# uCBoard.net
KiCad netlist of a schematic drawn in EAGLE
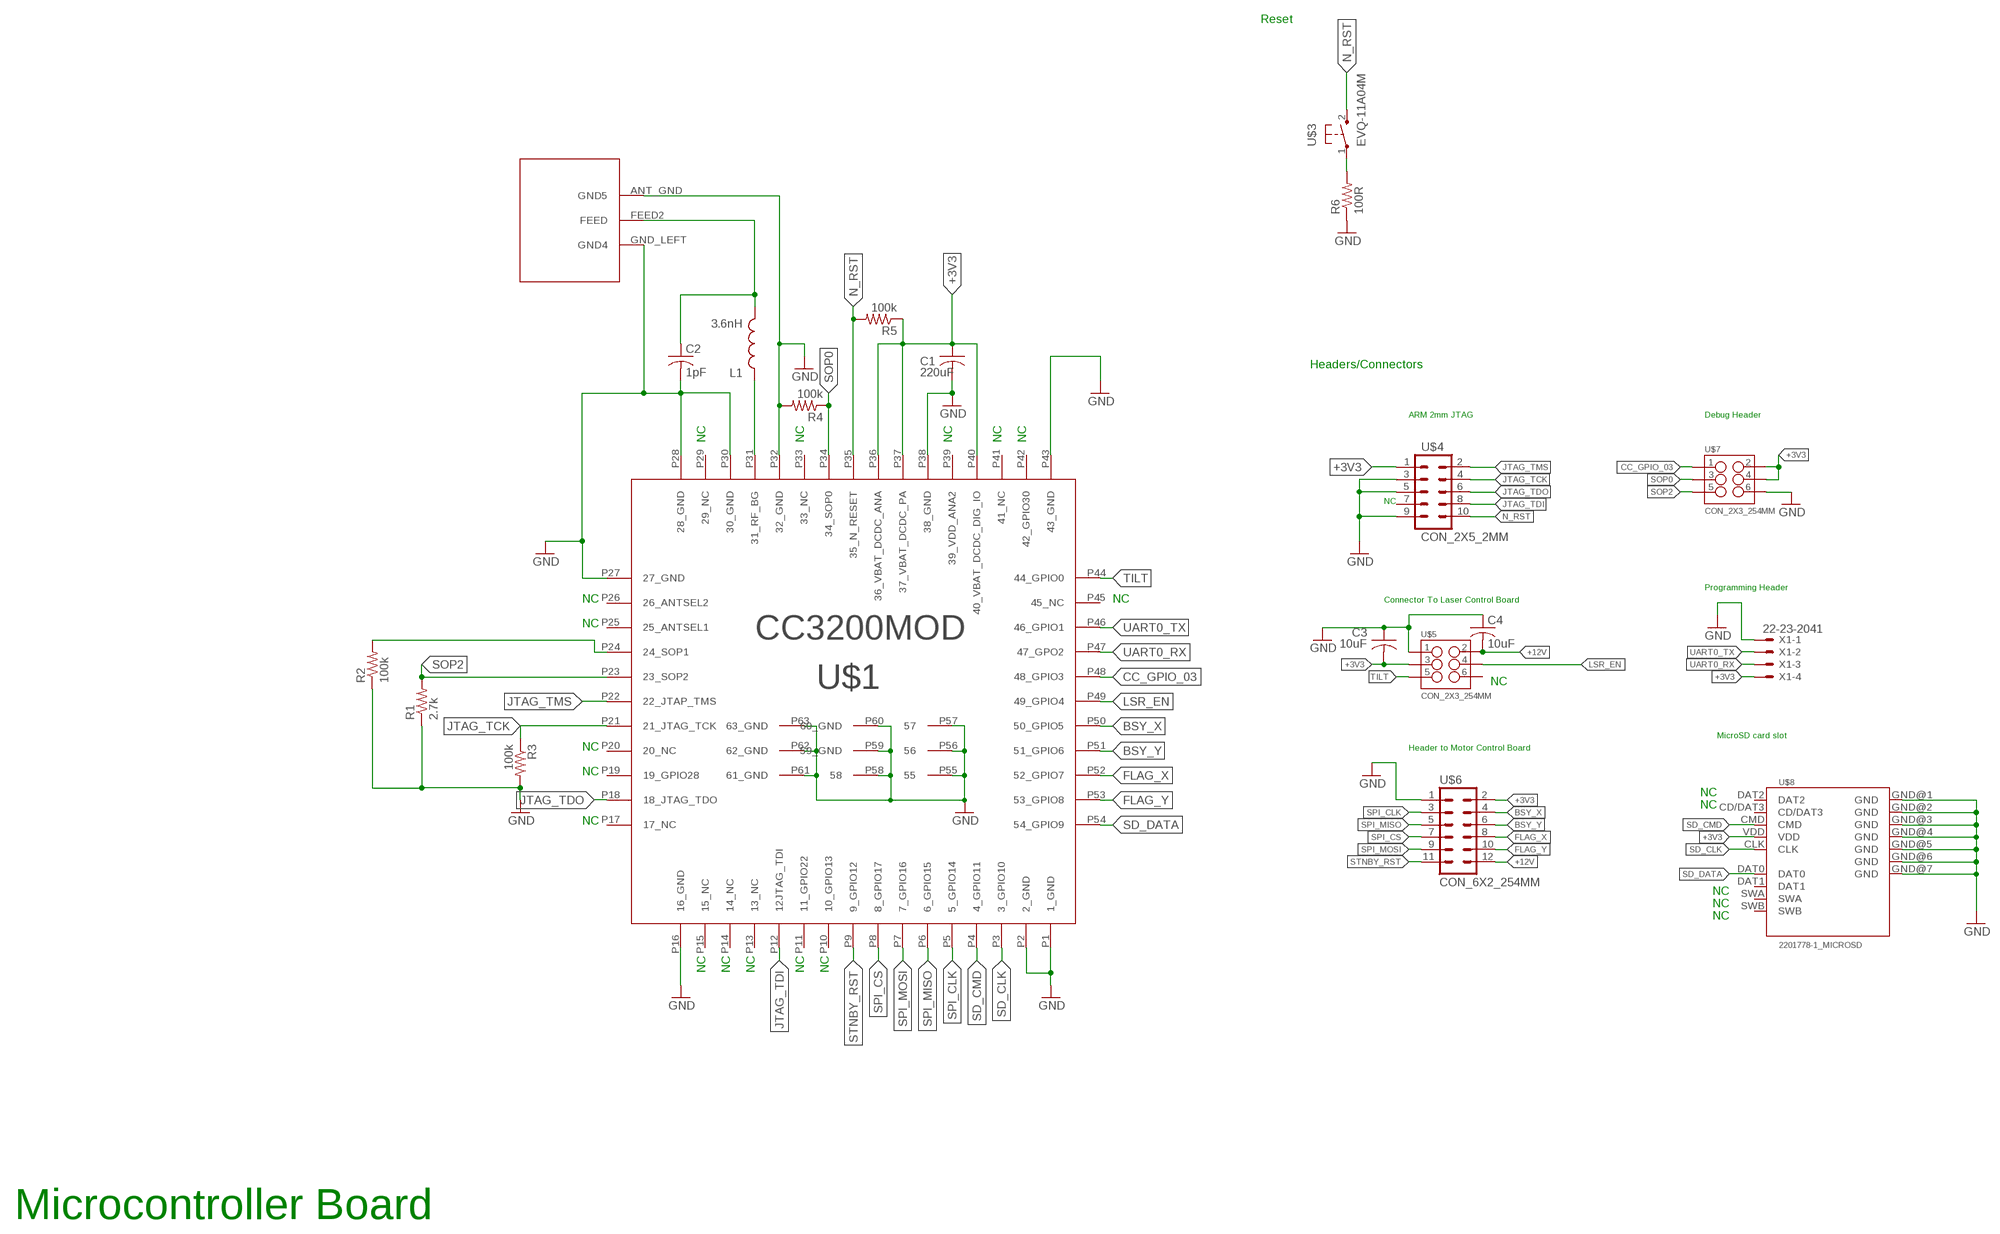
[diagram p0: schematic, sheet 1]

(export (version "E")
  (design (tool "Eeschema 10.0.6"))
  (components
    (comp (ref "C1")
      (value "220uF")
      (footprint "eagle-import:C1210")
      (libsource (lib "eagle-import") (part "C-USC1210"))
    )
    (comp (ref "C2")
      (value "1pF")
      (footprint "eagle-import:C0805")
      (libsource (lib "eagle-import") (part "resistor_C-USC0805"))
    )
    (comp (ref "C3")
      (value "10uF")
      (footprint "eagle-import:C0805")
      (libsource (lib "eagle-import") (part "resistor_C-USC0805"))
    )
    (comp (ref "C4")
      (value "10uF")
      (footprint "eagle-import:C0805")
      (libsource (lib "eagle-import") (part "resistor_C-USC0805"))
    )
    (comp (ref "L1")
      (value "3.6nH")
      (footprint "eagle-import:C0402")
      (libsource (lib "eagle-import") (part "INDUCTOR0402"))
    )
    (comp (ref "R1")
      (value "2.7k")
      (footprint "eagle-import:R0805")
      (libsource (lib "eagle-import") (part "R-US_R0805"))
    )
    (comp (ref "R2")
      (value "100k")
      (footprint "eagle-import:R0805")
      (libsource (lib "eagle-import") (part "R-US_R0805"))
    )
    (comp (ref "R3")
      (value "100k")
      (footprint "eagle-import:R0805")
      (libsource (lib "eagle-import") (part "R-US_R0805"))
    )
    (comp (ref "R4")
      (value "100k")
      (footprint "eagle-import:R0805")
      (libsource (lib "eagle-import") (part "R-US_R0805"))
    )
    (comp (ref "R5")
      (value "100k")
      (footprint "eagle-import:R0805")
      (libsource (lib "eagle-import") (part "R-US_R0805"))
    )
    (comp (ref "R6")
      (value "100R")
      (footprint "eagle-import:R0805")
      (libsource (lib "eagle-import") (part "R-US_R0805"))
    )
    (comp (ref "U$1")
      (value "CC3200")
      (footprint "eagle-import:CC3200MOD")
      (libsource (lib "eagle-import") (part "CC3200"))
    )
    (comp (ref "U$2")
      (value "ANT")
      (footprint "eagle-import:ANT")
      (libsource (lib "eagle-import") (part "ANT"))
    )
    (comp (ref "U$3")
      (value "EVQ-11A04M")
      (footprint "eagle-import:EVQ--11A04M")
      (libsource (lib "eagle-import") (part "EVQ-11A04M"))
    )
    (comp (ref "U$4")
      (value "CON_2X5_2MM")
      (footprint "eagle-import:CON_2X5_2MM")
      (libsource (lib "eagle-import") (part "CON_2X5_2MM"))
    )
    (comp (ref "U$5")
      (value "CON_2X3_254MM")
      (footprint "eagle-import:CON_2X3_254MM")
      (libsource (lib "eagle-import") (part "CON_2X3_254MM"))
    )
    (comp (ref "U$6")
      (value "CON_6X2_254MM")
      (footprint "eagle-import:CON_6X2_254MM")
      (libsource (lib "eagle-import") (part "CON_6X2_254MM"))
    )
    (comp (ref "U$7")
      (value "CON_2X3_254MM")
      (footprint "eagle-import:CON_2X3_254MM")
      (libsource (lib "eagle-import") (part "CON_2X3_254MM"))
    )
    (comp (ref "U$8")
      (value "2201778-1_MICROSD")
      (footprint "eagle-import:2201778-1")
      (libsource (lib "eagle-import") (part "2201778-1_MICROSD"))
    )
    (comp (ref "X1")
      (value "22-23-2041")
      (footprint "eagle-import:22-23-2041")
      (fields (field (name "MF") "MOLEX"))
      (libsource (lib "eagle-import") (part "22-23-2041"))
    )
  )
  (nets
    (net (code "1") (name "+3V3") (class "Default")
      (node (ref "C1") (pin "1") (pinfunction "1_1") (pintype "passive"))
      (node (ref "C3") (pin "2") (pinfunction "2_2") (pintype "passive"))
      (node (ref "R5") (pin "1") (pinfunction "1_1") (pintype "passive"))
      (node (ref "U$1") (pin "P36") (pinfunction "36_VBAT_DCDC_ANA_P36") (pintype "bidirectional"))
      (node (ref "U$1") (pin "P37") (pinfunction "37_VBAT_DCDC_PA_P37") (pintype "bidirectional"))
      (node (ref "U$1") (pin "P40") (pinfunction "40_VBAT_DCDC_DIG_IO_P40") (pintype "bidirectional"))
      (node (ref "U$4") (pin "1") (pinfunction "1_1") (pintype "passive"))
      (node (ref "U$5") (pin "3") (pinfunction "3_3") (pintype "bidirectional"))
      (node (ref "U$6") (pin "2") (pinfunction "2_2") (pintype "passive"))
      (node (ref "U$7") (pin "2") (pinfunction "2_2") (pintype "bidirectional"))
      (node (ref "U$7") (pin "4") (pinfunction "4_4") (pintype "bidirectional"))
      (node (ref "U$8") (pin "VDD") (pinfunction "VDD_VDD") (pintype "power_in"))
      (node (ref "X1") (pin "4") (pinfunction "S_4") (pintype "passive"))
    )
    (net (code "2") (name "+12V") (class "Default")
      (node (ref "C4") (pin "2") (pinfunction "2_2") (pintype "passive"))
      (node (ref "U$5") (pin "2") (pinfunction "2_2") (pintype "bidirectional"))
      (node (ref "U$6") (pin "12") (pinfunction "12_12") (pintype "passive"))
    )
    (net (code "3") (name "BSY_X") (class "Default")
      (node (ref "U$1") (pin "P50") (pinfunction "50_GPIO5_P50") (pintype "bidirectional"))
      (node (ref "U$6") (pin "4") (pinfunction "4_4") (pintype "passive"))
    )
    (net (code "4") (name "BSY_Y") (class "Default")
      (node (ref "U$1") (pin "P51") (pinfunction "51_GPIO6_P51") (pintype "bidirectional"))
      (node (ref "U$6") (pin "6") (pinfunction "6_6") (pintype "passive"))
    )
    (net (code "5") (name "CC_GPIO_03") (class "Default")
      (node (ref "U$1") (pin "P48") (pinfunction "48_GPIO3_P48") (pintype "bidirectional"))
      (node (ref "U$7") (pin "1") (pinfunction "1_1") (pintype "bidirectional"))
    )
    (net (code "6") (name "FLAG_X") (class "Default")
      (node (ref "U$1") (pin "P52") (pinfunction "52_GPIO7_P52") (pintype "bidirectional"))
      (node (ref "U$6") (pin "8") (pinfunction "8_8") (pintype "passive"))
    )
    (net (code "7") (name "FLAG_Y") (class "Default")
      (node (ref "U$1") (pin "P53") (pinfunction "53_GPIO8_P53") (pintype "bidirectional"))
      (node (ref "U$6") (pin "10") (pinfunction "10_10") (pintype "passive"))
    )
    (net (code "8") (name "GND") (class "Default")
      (node (ref "C1") (pin "2") (pinfunction "2_2") (pintype "passive"))
      (node (ref "C2") (pin "2") (pinfunction "2_2") (pintype "passive"))
      (node (ref "C3") (pin "1") (pinfunction "1_1") (pintype "passive"))
      (node (ref "C4") (pin "1") (pinfunction "1_1") (pintype "passive"))
      (node (ref "R1") (pin "1") (pinfunction "1_1") (pintype "passive"))
      (node (ref "R2") (pin "1") (pinfunction "1_1") (pintype "passive"))
      (node (ref "R3") (pin "2") (pinfunction "2_2") (pintype "passive"))
      (node (ref "R4") (pin "2") (pinfunction "2_2") (pintype "passive"))
      (node (ref "R6") (pin "1") (pinfunction "1_1") (pintype "passive"))
      (node (ref "U$1") (pin "P1") (pinfunction "1_GND_P1") (pintype "bidirectional"))
      (node (ref "U$1") (pin "P16") (pinfunction "16_GND_P16") (pintype "bidirectional"))
      (node (ref "U$1") (pin "P2") (pinfunction "2_GND_P2") (pintype "bidirectional"))
      (node (ref "U$1") (pin "P27") (pinfunction "27_GND_P27") (pintype "bidirectional"))
      (node (ref "U$1") (pin "P28") (pinfunction "28_GND_P28") (pintype "bidirectional"))
      (node (ref "U$1") (pin "P30") (pinfunction "30_GND_P30") (pintype "bidirectional"))
      (node (ref "U$1") (pin "P32") (pinfunction "32_GND_P32") (pintype "bidirectional"))
      (node (ref "U$1") (pin "P38") (pinfunction "38_GND_P38") (pintype "bidirectional"))
      (node (ref "U$1") (pin "P43") (pinfunction "43_GND_P43") (pintype "bidirectional"))
      (node (ref "U$1") (pin "P55") (pinfunction "55_P55") (pintype "bidirectional"))
      (node (ref "U$1") (pin "P56") (pinfunction "56_P56") (pintype "bidirectional"))
      (node (ref "U$1") (pin "P57") (pinfunction "57_P57") (pintype "bidirectional"))
      (node (ref "U$1") (pin "P58") (pinfunction "58_P58") (pintype "bidirectional"))
      (node (ref "U$1") (pin "P59") (pinfunction "59_GND_P59") (pintype "bidirectional"))
      (node (ref "U$1") (pin "P60") (pinfunction "60_GND_P60") (pintype "bidirectional"))
      (node (ref "U$1") (pin "P61") (pinfunction "61_GND_P61") (pintype "bidirectional"))
      (node (ref "U$1") (pin "P62") (pinfunction "62_GND_P62") (pintype "bidirectional"))
      (node (ref "U$1") (pin "P63") (pinfunction "63_GND_P63") (pintype "bidirectional"))
      (node (ref "U$2") (pin "ANT_GND") (pinfunction "GND5_ANT_GND") (pintype "bidirectional"))
      (node (ref "U$2") (pin "GND_LEFT") (pinfunction "GND4_GND_LEFT") (pintype "bidirectional"))
      (node (ref "U$4") (pin "3") (pinfunction "3_3") (pintype "passive"))
      (node (ref "U$4") (pin "5") (pinfunction "5_5") (pintype "passive"))
      (node (ref "U$4") (pin "9") (pinfunction "9_9") (pintype "passive"))
      (node (ref "U$5") (pin "1") (pinfunction "1_1") (pintype "bidirectional"))
      (node (ref "U$6") (pin "1") (pinfunction "1_1") (pintype "passive"))
      (node (ref "U$7") (pin "6") (pinfunction "6_6") (pintype "bidirectional"))
      (node (ref "U$8") (pin "GND@1") (pinfunction "GND_GND@1") (pintype "power_in"))
      (node (ref "U$8") (pin "GND@2") (pinfunction "GND_GND@2") (pintype "power_in"))
      (node (ref "U$8") (pin "GND@3") (pinfunction "GND_GND@3") (pintype "power_in"))
      (node (ref "U$8") (pin "GND@4") (pinfunction "GND_GND@4") (pintype "power_in"))
      (node (ref "U$8") (pin "GND@5") (pinfunction "GND_GND@5") (pintype "power_in"))
      (node (ref "U$8") (pin "GND@6") (pinfunction "GND_GND@6") (pintype "power_in"))
      (node (ref "U$8") (pin "GND@7") (pinfunction "GND_GND@7") (pintype "power_in"))
      (node (ref "X1") (pin "1") (pinfunction "S_1") (pintype "passive"))
    )
    (net (code "9") (name "JTAG_TCK") (class "Default")
      (node (ref "R3") (pin "1") (pinfunction "1_1") (pintype "passive"))
      (node (ref "U$1") (pin "P21") (pinfunction "21_JTAG_TCK_P21") (pintype "bidirectional"))
      (node (ref "U$4") (pin "4") (pinfunction "4_4") (pintype "passive"))
    )
    (net (code "10") (name "JTAG_TDI") (class "Default")
      (node (ref "U$1") (pin "P12") (pinfunction "12JTAG_TDI_P12") (pintype "bidirectional"))
      (node (ref "U$4") (pin "8") (pinfunction "8_8") (pintype "passive"))
    )
    (net (code "11") (name "JTAG_TDO") (class "Default")
      (node (ref "U$1") (pin "P18") (pinfunction "18_JTAG_TDO_P18") (pintype "bidirectional"))
      (node (ref "U$4") (pin "6") (pinfunction "6_6") (pintype "passive"))
    )
    (net (code "12") (name "JTAG_TMS") (class "Default")
      (node (ref "U$1") (pin "P22") (pinfunction "22_JTAP_TMS_P22") (pintype "bidirectional"))
      (node (ref "U$4") (pin "2") (pinfunction "2_2") (pintype "passive"))
    )
    (net (code "13") (name "LSR_EN") (class "Default")
      (node (ref "U$1") (pin "P49") (pinfunction "49_GPIO4_P49") (pintype "bidirectional"))
      (node (ref "U$5") (pin "4") (pinfunction "4_4") (pintype "bidirectional"))
    )
    (net (code "14") (name "N_RST") (class "Default")
      (node (ref "R5") (pin "2") (pinfunction "2_2") (pintype "passive"))
      (node (ref "U$1") (pin "P35") (pinfunction "35_N_RESET_P35") (pintype "bidirectional"))
      (node (ref "U$3") (pin "2") (pinfunction "2_2") (pintype "passive"))
      (node (ref "U$4") (pin "10") (pinfunction "10_10") (pintype "passive"))
    )
    (net (code "15") (name "Net-(R6-Pad2)") (class "Default")
      (node (ref "R6") (pin "2") (pinfunction "2_2") (pintype "passive"))
      (node (ref "U$3") (pin "1") (pinfunction "1_1") (pintype "passive"))
    )
    (net (code "16") (name "Net-(U$1-24_SOP1)") (class "Default")
      (node (ref "R2") (pin "2") (pinfunction "2_2") (pintype "passive"))
      (node (ref "U$1") (pin "P24") (pinfunction "24_SOP1_P24") (pintype "bidirectional"))
    )
    (net (code "17") (name "Net-(U$1-31_RF_BG)") (class "Default")
      (node (ref "L1") (pin "1") (pinfunction "1_1") (pintype "passive"))
      (node (ref "U$1") (pin "P31") (pinfunction "31_RF_BG_P31") (pintype "bidirectional"))
    )
    (net (code "18") (name "Net-(U$2-FEED)") (class "Default")
      (node (ref "C2") (pin "1") (pinfunction "1_1") (pintype "passive"))
      (node (ref "L1") (pin "2") (pinfunction "2_2") (pintype "passive"))
      (node (ref "U$2") (pin "FEED2") (pinfunction "FEED_FEED2") (pintype "bidirectional"))
    )
    (net (code "19") (name "SD_CLK") (class "Default")
      (node (ref "U$1") (pin "P3") (pinfunction "3_GPIO10_P3") (pintype "bidirectional"))
      (node (ref "U$8") (pin "CLK") (pinfunction "CLK_CLK") (pintype "bidirectional"))
    )
    (net (code "20") (name "SD_CMD") (class "Default")
      (node (ref "U$1") (pin "P4") (pinfunction "4_GPIO11_P4") (pintype "bidirectional"))
      (node (ref "U$8") (pin "CMD") (pinfunction "CMD_CMD") (pintype "bidirectional"))
    )
    (net (code "21") (name "SD_DATA") (class "Default")
      (node (ref "U$1") (pin "P54") (pinfunction "54_GPIO9_P54") (pintype "bidirectional"))
      (node (ref "U$8") (pin "DAT0") (pinfunction "DAT0_DAT0") (pintype "bidirectional"))
    )
    (net (code "22") (name "SOP0") (class "Default")
      (node (ref "R4") (pin "1") (pinfunction "1_1") (pintype "passive"))
      (node (ref "U$1") (pin "P34") (pinfunction "34_SOP0_P34") (pintype "bidirectional"))
      (node (ref "U$7") (pin "3") (pinfunction "3_3") (pintype "bidirectional"))
    )
    (net (code "23") (name "SOP2") (class "Default")
      (node (ref "R1") (pin "2") (pinfunction "2_2") (pintype "passive"))
      (node (ref "U$1") (pin "P23") (pinfunction "23_SOP2_P23") (pintype "bidirectional"))
      (node (ref "U$7") (pin "5") (pinfunction "5_5") (pintype "bidirectional"))
    )
    (net (code "24") (name "SPI_CLK") (class "Default")
      (node (ref "U$1") (pin "P5") (pinfunction "5_GPIO14_P5") (pintype "bidirectional"))
      (node (ref "U$6") (pin "3") (pinfunction "3_3") (pintype "passive"))
    )
    (net (code "25") (name "SPI_CS") (class "Default")
      (node (ref "U$1") (pin "P8") (pinfunction "8_GPIO17_P8") (pintype "bidirectional"))
      (node (ref "U$6") (pin "7") (pinfunction "7_7") (pintype "passive"))
    )
    (net (code "26") (name "SPI_MISO") (class "Default")
      (node (ref "U$1") (pin "P6") (pinfunction "6_GPIO15_P6") (pintype "bidirectional"))
      (node (ref "U$6") (pin "5") (pinfunction "5_5") (pintype "passive"))
    )
    (net (code "27") (name "SPI_MOSI") (class "Default")
      (node (ref "U$1") (pin "P7") (pinfunction "7_GPIO16_P7") (pintype "bidirectional"))
      (node (ref "U$6") (pin "9") (pinfunction "9_9") (pintype "passive"))
    )
    (net (code "28") (name "STNBY_RST") (class "Default")
      (node (ref "U$1") (pin "P9") (pinfunction "9_GPIO12_P9") (pintype "bidirectional"))
      (node (ref "U$6") (pin "11") (pinfunction "11_11") (pintype "passive"))
    )
    (net (code "29") (name "TILT") (class "Default")
      (node (ref "U$1") (pin "P44") (pinfunction "44_GPIO0_P44") (pintype "bidirectional"))
      (node (ref "U$5") (pin "5") (pinfunction "5_5") (pintype "bidirectional"))
    )
    (net (code "30") (name "UART0_RX") (class "Default")
      (node (ref "U$1") (pin "P47") (pinfunction "47_GPO2_P47") (pintype "bidirectional"))
      (node (ref "X1") (pin "3") (pinfunction "S_3") (pintype "passive"))
    )
    (net (code "31") (name "UART0_TX") (class "Default")
      (node (ref "U$1") (pin "P46") (pinfunction "46_GPIO1_P46") (pintype "bidirectional"))
      (node (ref "X1") (pin "2") (pinfunction "S_2") (pintype "passive"))
    )
    (net (code "32") (name "unconnected-(U$1-10_GPIO13-PadP10)") (class "Default")
      (node (ref "U$1") (pin "P10") (pinfunction "10_GPIO13_P10") (pintype "bidirectional"))
    )
    (net (code "33") (name "unconnected-(U$1-11_GPIO22-PadP11)") (class "Default")
      (node (ref "U$1") (pin "P11") (pinfunction "11_GPIO22_P11") (pintype "bidirectional"))
    )
    (net (code "34") (name "unconnected-(U$1-13_NC-PadP13)") (class "Default")
      (node (ref "U$1") (pin "P13") (pinfunction "13_NC_P13") (pintype "bidirectional"))
    )
    (net (code "35") (name "unconnected-(U$1-14_NC-PadP14)") (class "Default")
      (node (ref "U$1") (pin "P14") (pinfunction "14_NC_P14") (pintype "bidirectional"))
    )
    (net (code "36") (name "unconnected-(U$1-15_NC-PadP15)") (class "Default")
      (node (ref "U$1") (pin "P15") (pinfunction "15_NC_P15") (pintype "bidirectional"))
    )
    (net (code "37") (name "unconnected-(U$1-17_NC-PadP17)") (class "Default")
      (node (ref "U$1") (pin "P17") (pinfunction "17_NC_P17") (pintype "bidirectional"))
    )
    (net (code "38") (name "unconnected-(U$1-19_GPIO28-PadP19)") (class "Default")
      (node (ref "U$1") (pin "P19") (pinfunction "19_GPIO28_P19") (pintype "bidirectional"))
    )
    (net (code "39") (name "unconnected-(U$1-20_NC-PadP20)") (class "Default")
      (node (ref "U$1") (pin "P20") (pinfunction "20_NC_P20") (pintype "bidirectional"))
    )
    (net (code "40") (name "unconnected-(U$1-25_ANTSEL1-PadP25)") (class "Default")
      (node (ref "U$1") (pin "P25") (pinfunction "25_ANTSEL1_P25") (pintype "bidirectional"))
    )
    (net (code "41") (name "unconnected-(U$1-26_ANTSEL2-PadP26)") (class "Default")
      (node (ref "U$1") (pin "P26") (pinfunction "26_ANTSEL2_P26") (pintype "bidirectional"))
    )
    (net (code "42") (name "unconnected-(U$1-29_NC-PadP29)") (class "Default")
      (node (ref "U$1") (pin "P29") (pinfunction "29_NC_P29") (pintype "bidirectional"))
    )
    (net (code "43") (name "unconnected-(U$1-33_NC-PadP33)") (class "Default")
      (node (ref "U$1") (pin "P33") (pinfunction "33_NC_P33") (pintype "bidirectional"))
    )
    (net (code "44") (name "unconnected-(U$1-39_VDD_ANA2-PadP39)") (class "Default")
      (node (ref "U$1") (pin "P39") (pinfunction "39_VDD_ANA2_P39") (pintype "bidirectional"))
    )
    (net (code "45") (name "unconnected-(U$1-41_NC-PadP41)") (class "Default")
      (node (ref "U$1") (pin "P41") (pinfunction "41_NC_P41") (pintype "bidirectional"))
    )
    (net (code "46") (name "unconnected-(U$1-42_GPIO30-PadP42)") (class "Default")
      (node (ref "U$1") (pin "P42") (pinfunction "42_GPIO30_P42") (pintype "bidirectional"))
    )
    (net (code "47") (name "unconnected-(U$1-45_NC-PadP45)") (class "Default")
      (node (ref "U$1") (pin "P45") (pinfunction "45_NC_P45") (pintype "bidirectional"))
    )
    (net (code "48") (name "unconnected-(U$4-Pad7)") (class "Default")
      (node (ref "U$4") (pin "7") (pinfunction "7_7") (pintype "passive"))
    )
    (net (code "49") (name "unconnected-(U$5-Pad6)") (class "Default")
      (node (ref "U$5") (pin "6") (pinfunction "6_6") (pintype "bidirectional"))
    )
    (net (code "50") (name "unconnected-(U$8-PadCD{slash}DAT3)") (class "Default")
      (node (ref "U$8") (pin "CD/DAT3") (pinfunction "CD/DAT3_CD/DAT3") (pintype "bidirectional"))
    )
    (net (code "51") (name "unconnected-(U$8-PadDAT1)") (class "Default")
      (node (ref "U$8") (pin "DAT1") (pinfunction "DAT1_DAT1") (pintype "bidirectional"))
    )
    (net (code "52") (name "unconnected-(U$8-PadDAT2)") (class "Default")
      (node (ref "U$8") (pin "DAT2") (pinfunction "DAT2_DAT2") (pintype "bidirectional"))
    )
    (net (code "53") (name "unconnected-(U$8-PadSWA)") (class "Default")
      (node (ref "U$8") (pin "SWA") (pinfunction "SWA_SWA") (pintype "bidirectional"))
    )
    (net (code "54") (name "unconnected-(U$8-PadSWB)") (class "Default")
      (node (ref "U$8") (pin "SWB") (pinfunction "SWB_SWB") (pintype "bidirectional"))
    )
  )
)
